# 1ButtonSwitch_ItsyBitsyM0_Rev1_0.net
KiCad netlist of a schematic drawn in EAGLE
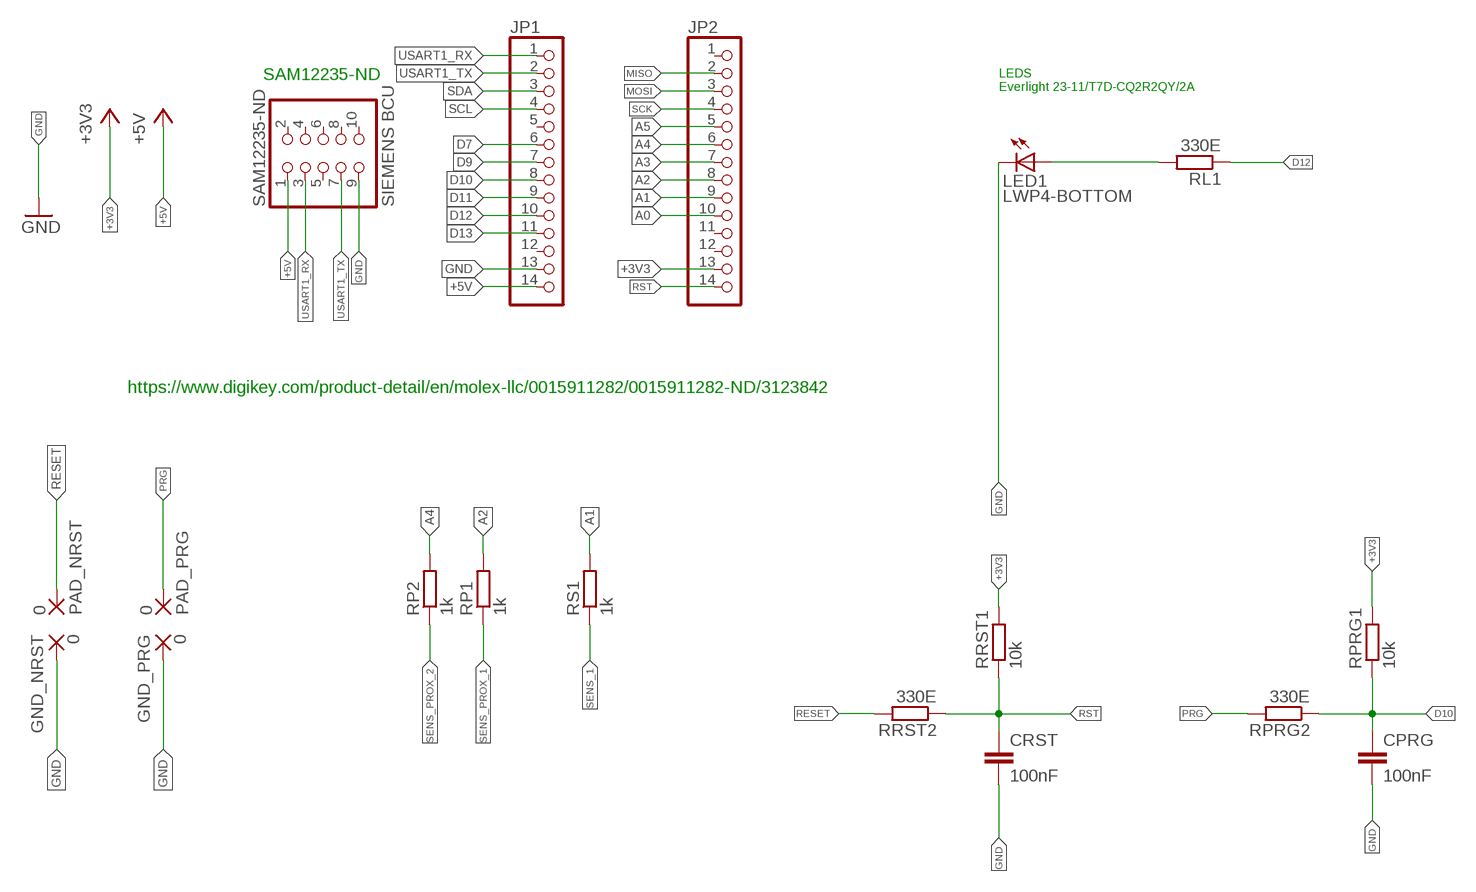
[diagram p0: schematic, sheet 1]

(export (version "E")
  (design (tool "Eeschema 10.0.6"))
  (components
    (comp (ref "CPRG")
      (value "100nF")
      (footprint "eagle-import:C1206")
      (libsource (lib "eagle-import") (part "C-EUC1206"))
    )
    (comp (ref "CRST")
      (value "100nF")
      (footprint "eagle-import:C1206")
      (libsource (lib "eagle-import") (part "C-EUC1206"))
    )
    (comp (ref "GND_NRST")
      (value "0")
      (footprint "eagle-import:SMD2,54-5,08")
      (libsource (lib "eagle-import") (part "SMD5"))
    )
    (comp (ref "GND_PRG")
      (value "0")
      (footprint "eagle-import:SMD2,54-5,08")
      (libsource (lib "eagle-import") (part "SMD5"))
    )
    (comp (ref "JP1")
      (value "PINHD-1X141X14_SMT")
      (footprint "eagle-import:1X14_SMT")
      (libsource (lib "eagle-import") (part "PINHD-1X141X14_SMT"))
    )
    (comp (ref "JP2")
      (value "PINHD-1X141X14_SMT")
      (footprint "eagle-import:1X14_SMT")
      (libsource (lib "eagle-import") (part "PINHD-1X141X14_SMT"))
    )
    (comp (ref "LED1")
      (value "LWP4-BOTTOM")
      (footprint "eagle-import:P47F-BOTTOM")
      (libsource (lib "eagle-import") (part "P4-BOTTOMLW"))
    )
    (comp (ref "PAD_NRST")
      (value "0")
      (footprint "eagle-import:SMD2,54-5,08")
      (libsource (lib "eagle-import") (part "SMD5"))
    )
    (comp (ref "PAD_PRG")
      (value "0")
      (footprint "eagle-import:SMD2,54-5,08")
      (libsource (lib "eagle-import") (part "SMD5"))
    )
    (comp (ref "RL1")
      (value "330E")
      (footprint "eagle-import:R1206")
      (libsource (lib "eagle-import") (part "R-EU_R1206"))
    )
    (comp (ref "RP1")
      (value "1k")
      (footprint "eagle-import:R1206")
      (libsource (lib "eagle-import") (part "R-EU_R1206"))
    )
    (comp (ref "RP2")
      (value "1k")
      (footprint "eagle-import:R1206")
      (libsource (lib "eagle-import") (part "R-EU_R1206"))
    )
    (comp (ref "RPRG1")
      (value "10k")
      (footprint "eagle-import:R1206")
      (libsource (lib "eagle-import") (part "R-EU_R1206"))
    )
    (comp (ref "RPRG2")
      (value "330E")
      (footprint "eagle-import:R1206")
      (libsource (lib "eagle-import") (part "R-EU_R1206"))
    )
    (comp (ref "RRST1")
      (value "10k")
      (footprint "eagle-import:R1206")
      (libsource (lib "eagle-import") (part "R-EU_R1206"))
    )
    (comp (ref "RRST2")
      (value "330E")
      (footprint "eagle-import:R1206")
      (libsource (lib "eagle-import") (part "R-EU_R1206"))
    )
    (comp (ref "RS1")
      (value "1k")
      (footprint "eagle-import:R1206")
      (libsource (lib "eagle-import") (part "R-EU_R1206"))
    )
    (comp (ref "SAM12235-ND")
      (value "SIEMENS BCU")
      (footprint "eagle-import:2X05SMD")
      (libsource (lib "eagle-import") (part "PINHD-2X5_2.54-SMD"))
    )
  )
  (nets
    (net (code "1") (name "+3V3") (class "Default")
      (node (ref "JP2") (pin "13") (pinfunction "13_13") (pintype "passive"))
      (node (ref "RPRG1") (pin "2") (pinfunction "2_2") (pintype "passive"))
      (node (ref "RRST1") (pin "2") (pinfunction "2_2") (pintype "passive"))
    )
    (net (code "2") (name "+5V") (class "Default")
      (node (ref "JP1") (pin "14") (pinfunction "14_14") (pintype "passive"))
      (node (ref "SAM12235-ND") (pin "1") (pinfunction "1_1") (pintype "passive"))
    )
    (net (code "3") (name "A0") (class "Default")
      (node (ref "JP2") (pin "10") (pinfunction "10_10") (pintype "passive"))
    )
    (net (code "4") (name "A1") (class "Default")
      (node (ref "JP2") (pin "9") (pinfunction "9_9") (pintype "passive"))
      (node (ref "RS1") (pin "2") (pinfunction "2_2") (pintype "passive"))
    )
    (net (code "5") (name "A2") (class "Default")
      (node (ref "JP2") (pin "8") (pinfunction "8_8") (pintype "passive"))
      (node (ref "RP1") (pin "2") (pinfunction "2_2") (pintype "passive"))
    )
    (net (code "6") (name "A3") (class "Default")
      (node (ref "JP2") (pin "7") (pinfunction "7_7") (pintype "passive"))
    )
    (net (code "7") (name "A4") (class "Default")
      (node (ref "JP2") (pin "6") (pinfunction "6_6") (pintype "passive"))
      (node (ref "RP2") (pin "2") (pinfunction "2_2") (pintype "passive"))
    )
    (net (code "8") (name "A5") (class "Default")
      (node (ref "JP2") (pin "5") (pinfunction "5_5") (pintype "passive"))
    )
    (net (code "9") (name "D7") (class "Default")
      (node (ref "JP1") (pin "6") (pinfunction "6_6") (pintype "passive"))
    )
    (net (code "10") (name "D9") (class "Default")
      (node (ref "JP1") (pin "7") (pinfunction "7_7") (pintype "passive"))
    )
    (net (code "11") (name "D10") (class "Default")
      (node (ref "CPRG") (pin "1") (pinfunction "1_1") (pintype "passive"))
      (node (ref "JP1") (pin "8") (pinfunction "8_8") (pintype "passive"))
      (node (ref "RPRG1") (pin "1") (pinfunction "1_1") (pintype "passive"))
      (node (ref "RPRG2") (pin "1") (pinfunction "1_1") (pintype "passive"))
    )
    (net (code "12") (name "D11") (class "Default")
      (node (ref "JP1") (pin "9") (pinfunction "9_9") (pintype "passive"))
    )
    (net (code "13") (name "D12") (class "Default")
      (node (ref "JP1") (pin "10") (pinfunction "10_10") (pintype "passive"))
      (node (ref "RL1") (pin "1") (pinfunction "1_1") (pintype "passive"))
    )
    (net (code "14") (name "D13") (class "Default")
      (node (ref "JP1") (pin "11") (pinfunction "11_11") (pintype "passive"))
    )
    (net (code "15") (name "GND") (class "Default")
      (node (ref "CPRG") (pin "2") (pinfunction "2_2") (pintype "passive"))
      (node (ref "CRST") (pin "2") (pinfunction "2_2") (pintype "passive"))
      (node (ref "GND_NRST") (pin "1") (pinfunction "P_1") (pintype "passive"))
      (node (ref "GND_PRG") (pin "1") (pinfunction "P_1") (pintype "passive"))
      (node (ref "JP1") (pin "13") (pinfunction "13_13") (pintype "passive"))
      (node (ref "LED1") (pin "C") (pinfunction "C_C") (pintype "passive"))
      (node (ref "SAM12235-ND") (pin "9") (pinfunction "9_9") (pintype "passive"))
    )
    (net (code "16") (name "MISO") (class "Default")
      (node (ref "JP2") (pin "2") (pinfunction "2_2") (pintype "passive"))
    )
    (net (code "17") (name "MOSI") (class "Default")
      (node (ref "JP2") (pin "3") (pinfunction "3_3") (pintype "passive"))
    )
    (net (code "18") (name "Net-(LED1-PadA)") (class "Default")
      (node (ref "LED1") (pin "A") (pinfunction "A_A") (pintype "passive"))
      (node (ref "RL1") (pin "2") (pinfunction "2_2") (pintype "passive"))
    )
    (net (code "19") (name "PRG") (class "Default")
      (node (ref "PAD_PRG") (pin "1") (pinfunction "P_1") (pintype "passive"))
      (node (ref "RPRG2") (pin "2") (pinfunction "2_2") (pintype "passive"))
    )
    (net (code "20") (name "RESET") (class "Default")
      (node (ref "PAD_NRST") (pin "1") (pinfunction "P_1") (pintype "passive"))
      (node (ref "RRST2") (pin "2") (pinfunction "2_2") (pintype "passive"))
    )
    (net (code "21") (name "RST") (class "Default")
      (node (ref "CRST") (pin "1") (pinfunction "1_1") (pintype "passive"))
      (node (ref "JP2") (pin "14") (pinfunction "14_14") (pintype "passive"))
      (node (ref "RRST1") (pin "1") (pinfunction "1_1") (pintype "passive"))
      (node (ref "RRST2") (pin "1") (pinfunction "1_1") (pintype "passive"))
    )
    (net (code "22") (name "SCK") (class "Default")
      (node (ref "JP2") (pin "4") (pinfunction "4_4") (pintype "passive"))
    )
    (net (code "23") (name "SCL") (class "Default")
      (node (ref "JP1") (pin "4") (pinfunction "4_4") (pintype "passive"))
    )
    (net (code "24") (name "SDA") (class "Default")
      (node (ref "JP1") (pin "3") (pinfunction "3_3") (pintype "passive"))
    )
    (net (code "25") (name "SENS_1") (class "Default")
      (node (ref "RS1") (pin "1") (pinfunction "1_1") (pintype "passive"))
    )
    (net (code "26") (name "SENS_PROX_1") (class "Default")
      (node (ref "RP1") (pin "1") (pinfunction "1_1") (pintype "passive"))
    )
    (net (code "27") (name "SENS_PROX_2") (class "Default")
      (node (ref "RP2") (pin "1") (pinfunction "1_1") (pintype "passive"))
    )
    (net (code "28") (name "USART1_RX") (class "Default")
      (node (ref "JP1") (pin "1") (pinfunction "1_1") (pintype "passive"))
      (node (ref "SAM12235-ND") (pin "3") (pinfunction "3_3") (pintype "passive"))
    )
    (net (code "29") (name "USART1_TX") (class "Default")
      (node (ref "JP1") (pin "2") (pinfunction "2_2") (pintype "passive"))
      (node (ref "SAM12235-ND") (pin "7") (pinfunction "7_7") (pintype "passive"))
    )
    (net (code "30") (name "unconnected-(JP1-Pad5)") (class "Default")
      (node (ref "JP1") (pin "5") (pinfunction "5_5") (pintype "passive"))
    )
    (net (code "31") (name "unconnected-(JP1-Pad12)") (class "Default")
      (node (ref "JP1") (pin "12") (pinfunction "12_12") (pintype "passive"))
    )
    (net (code "32") (name "unconnected-(JP2-Pad1)") (class "Default")
      (node (ref "JP2") (pin "1") (pinfunction "1_1") (pintype "passive"))
    )
    (net (code "33") (name "unconnected-(JP2-Pad11)") (class "Default")
      (node (ref "JP2") (pin "11") (pinfunction "11_11") (pintype "passive"))
    )
    (net (code "34") (name "unconnected-(JP2-Pad12)") (class "Default")
      (node (ref "JP2") (pin "12") (pinfunction "12_12") (pintype "passive"))
    )
    (net (code "35") (name "unconnected-(SAM12235-ND-Pad2)") (class "Default")
      (node (ref "SAM12235-ND") (pin "2") (pinfunction "2_2") (pintype "passive"))
    )
    (net (code "36") (name "unconnected-(SAM12235-ND-Pad4)") (class "Default")
      (node (ref "SAM12235-ND") (pin "4") (pinfunction "4_4") (pintype "passive"))
    )
    (net (code "37") (name "unconnected-(SAM12235-ND-Pad5)") (class "Default")
      (node (ref "SAM12235-ND") (pin "5") (pinfunction "5_5") (pintype "passive"))
    )
    (net (code "38") (name "unconnected-(SAM12235-ND-Pad6)") (class "Default")
      (node (ref "SAM12235-ND") (pin "6") (pinfunction "6_6") (pintype "passive"))
    )
    (net (code "39") (name "unconnected-(SAM12235-ND-Pad8)") (class "Default")
      (node (ref "SAM12235-ND") (pin "8") (pinfunction "8_8") (pintype "passive"))
    )
    (net (code "40") (name "unconnected-(SAM12235-ND-Pad10)") (class "Default")
      (node (ref "SAM12235-ND") (pin "10") (pinfunction "10_10") (pintype "passive"))
    )
  )
)
